# LPF_Schematic.net
KiCad netlist of a schematic drawn in EAGLE
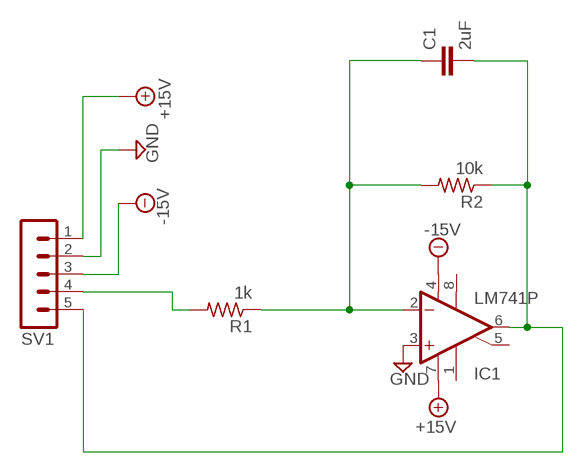
[diagram p0: schematic, sheet 1]

(export (version "E")
  (design (tool "Eeschema 10.0.6"))
  (components
    (comp (ref "C1")
      (value "2uF")
      (footprint "eagle-import:C0603")
      (libsource (lib "eagle-import") (part "C-EUC0603"))
    )
    (comp (ref "IC1")
      (value "LM741P")
      (footprint "eagle-import:DIL08")
      (libsource (lib "eagle-import") (part "741PLM"))
    )
    (comp (ref "R1")
      (value "1k")
      (footprint "eagle-import:R0603")
      (libsource (lib "eagle-import") (part "R-US_R0603"))
    )
    (comp (ref "R2")
      (value "10k")
      (footprint "eagle-import:R0603")
      (libsource (lib "eagle-import") (part "R-US_R0603"))
    )
    (comp (ref "SV1")
      (value "MA05-1")
      (footprint "eagle-import:MA05-1")
      (libsource (lib "eagle-import") (part "MA05-1"))
    )
  )
  (nets
    (net (code "1") (name "+15V") (class "Default")
      (node (ref "IC1") (pin "7") (pinfunction "V+_7") (pintype "power_in"))
      (node (ref "SV1") (pin "1") (pinfunction "1_1") (pintype "passive"))
    )
    (net (code "2") (name "-15V") (class "Default")
      (node (ref "IC1") (pin "4") (pinfunction "V-_4") (pintype "power_in"))
      (node (ref "SV1") (pin "3") (pinfunction "3_3") (pintype "passive"))
    )
    (net (code "3") (name "GND") (class "Default")
      (node (ref "IC1") (pin "3") (pinfunction "+IN_3") (pintype "input"))
      (node (ref "SV1") (pin "2") (pinfunction "2_2") (pintype "passive"))
    )
    (net (code "4") (name "Net-(IC1--IN)") (class "Default")
      (node (ref "C1") (pin "1") (pinfunction "1_1") (pintype "passive"))
      (node (ref "IC1") (pin "2") (pinfunction "-IN_2") (pintype "input"))
      (node (ref "R1") (pin "1") (pinfunction "1_1") (pintype "passive"))
      (node (ref "R2") (pin "2") (pinfunction "2_2") (pintype "passive"))
    )
    (net (code "5") (name "Net-(IC1-OUT)") (class "Default")
      (node (ref "C1") (pin "2") (pinfunction "2_2") (pintype "passive"))
      (node (ref "IC1") (pin "6") (pinfunction "OUT_6") (pintype "output"))
      (node (ref "R2") (pin "1") (pinfunction "1_1") (pintype "passive"))
      (node (ref "SV1") (pin "5") (pinfunction "5_5") (pintype "passive"))
    )
    (net (code "6") (name "Net-(R1-Pad2)") (class "Default")
      (node (ref "R1") (pin "2") (pinfunction "2_2") (pintype "passive"))
      (node (ref "SV1") (pin "4") (pinfunction "4_4") (pintype "passive"))
    )
    (net (code "7") (name "unconnected-(IC1-ON1-Pad1)") (class "Default")
      (node (ref "IC1") (pin "1") (pinfunction "ON1_1") (pintype "passive"))
    )
    (net (code "8") (name "unconnected-(IC1-ON2-Pad5)") (class "Default")
      (node (ref "IC1") (pin "5") (pinfunction "ON2_5") (pintype "passive"))
    )
    (net (code "9") (name "unconnected-(IC1-OPT-Pad8)") (class "Default")
      (node (ref "IC1") (pin "8") (pinfunction "OPT_8") (pintype "passive"))
    )
  )
)
